# Interface.net
KiCad netlist of a schematic drawn in Altium Designer
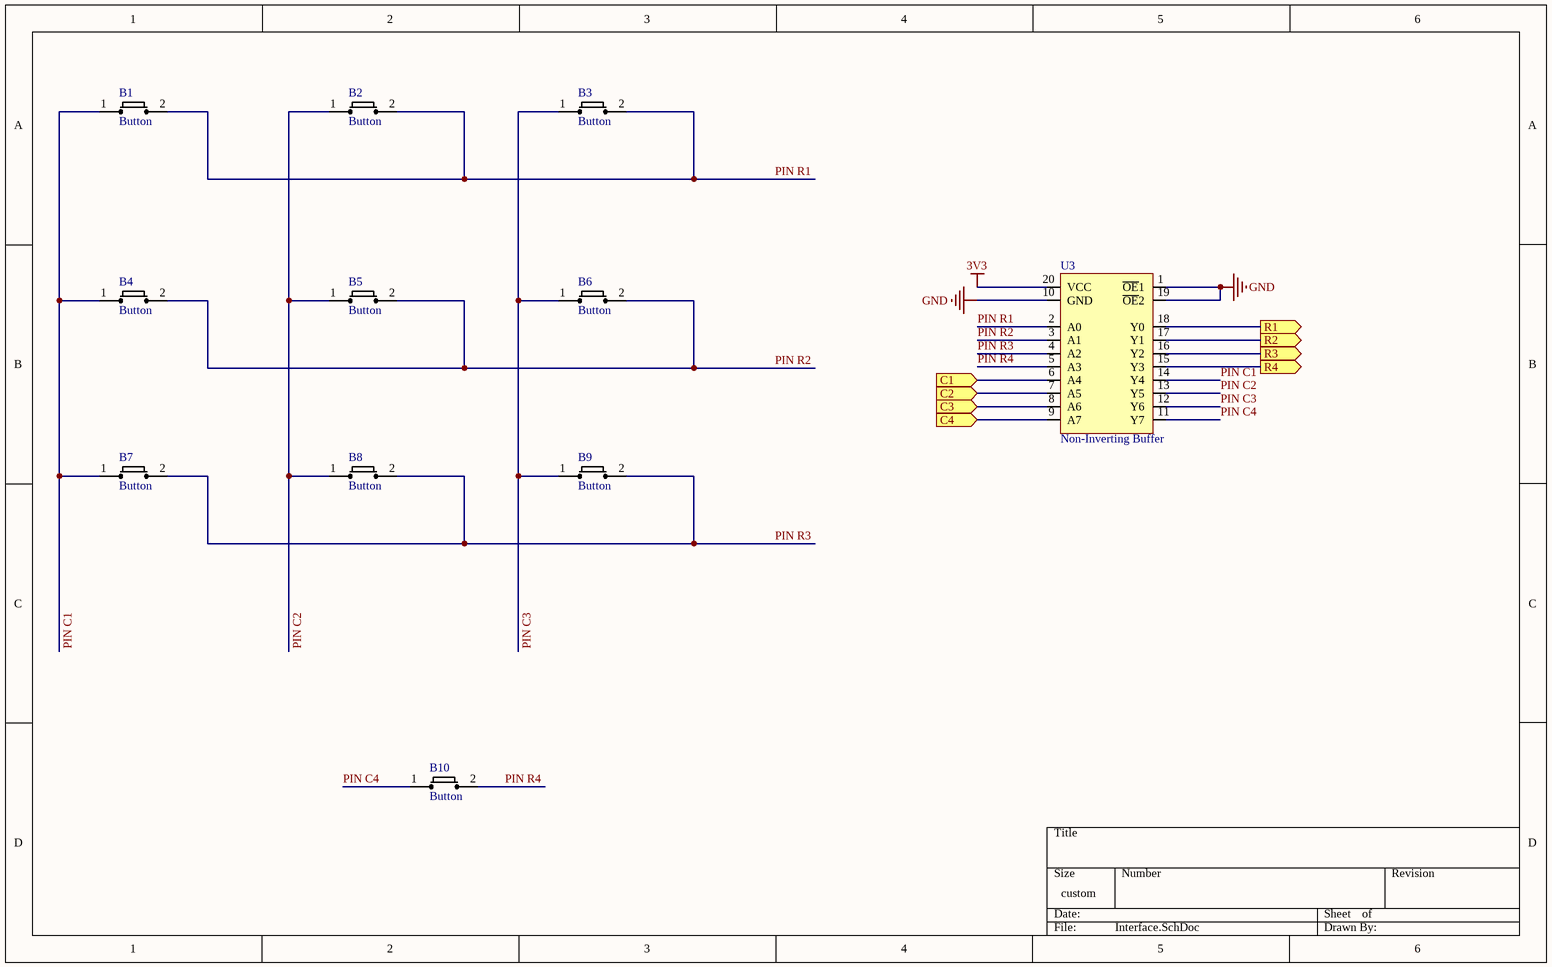
[diagram p0: Interface.SchDoc]

(export (version "E")
  (design (tool "Eeschema 10.0.6"))
  (components
    (comp (ref "B1")
      (value "Button")
      (footprint "BUTTON_B3F_SMD")
      (description "6x6mm, TH, 2 Pins")
      (libsource (lib "Altium Lib") (part "Button"))
    )
    (comp (ref "B2")
      (value "Button")
      (footprint "BUTTON_B3F_SMD")
      (description "6x6mm, TH, 2 Pins")
      (libsource (lib "Altium Lib") (part "Button"))
    )
    (comp (ref "B3")
      (value "Button")
      (footprint "BUTTON_B3F_SMD")
      (description "6x6mm, TH, 2 Pins")
      (libsource (lib "Altium Lib") (part "Button"))
    )
    (comp (ref "B4")
      (value "Button")
      (footprint "BUTTON_B3F_SMD")
      (description "6x6mm, TH, 2 Pins")
      (libsource (lib "Altium Lib") (part "Button"))
    )
    (comp (ref "B5")
      (value "Button")
      (footprint "BUTTON_B3F_SMD")
      (description "6x6mm, TH, 2 Pins")
      (libsource (lib "Altium Lib") (part "Button"))
    )
    (comp (ref "B6")
      (value "Button")
      (footprint "BUTTON_B3F_SMD")
      (description "6x6mm, TH, 2 Pins")
      (libsource (lib "Altium Lib") (part "Button"))
    )
    (comp (ref "B7")
      (value "Button")
      (footprint "BUTTON_B3F_SMD")
      (description "6x6mm, TH, 2 Pins")
      (libsource (lib "Altium Lib") (part "Button"))
    )
    (comp (ref "B8")
      (value "Button")
      (footprint "BUTTON_B3F_SMD")
      (description "6x6mm, TH, 2 Pins")
      (libsource (lib "Altium Lib") (part "Button"))
    )
    (comp (ref "B9")
      (value "Button")
      (footprint "BUTTON_B3F_SMD")
      (description "6x6mm, TH, 2 Pins")
      (libsource (lib "Altium Lib") (part "Button"))
    )
    (comp (ref "B10")
      (value "Button")
      (footprint "BUTTON_B3F_SMD")
      (description "6x6mm, TH, 2 Pins")
      (libsource (lib "Altium Lib") (part "Button"))
    )
    (comp (ref "U3")
      (value "Non-Inverting Buffer")
      (footprint "DIP_20")
      (libsource (lib "Altium Lib") (part "74HC541"))
    )
  )
  (nets
    (net (code "1") (name "/C1") (class "Default")
      (node (ref "U3") (pin "6") (pinfunction "A4_6") (pintype "passive"))
    )
    (net (code "2") (name "/C2") (class "Default")
      (node (ref "U3") (pin "7") (pinfunction "A5_7") (pintype "passive"))
    )
    (net (code "3") (name "/C3") (class "Default")
      (node (ref "U3") (pin "8") (pinfunction "A6_8") (pintype "passive"))
    )
    (net (code "4") (name "/C4") (class "Default")
      (node (ref "U3") (pin "9") (pinfunction "A7_9") (pintype "passive"))
    )
    (net (code "5") (name "/PIN C1") (class "Default")
      (node (ref "B1") (pin "1") (pinfunction "1_1") (pintype "passive"))
      (node (ref "B4") (pin "1") (pinfunction "1_1") (pintype "passive"))
      (node (ref "B7") (pin "1") (pinfunction "1_1") (pintype "passive"))
      (node (ref "U3") (pin "14") (pinfunction "Y4_14") (pintype "passive"))
    )
    (net (code "6") (name "/PIN C2") (class "Default")
      (node (ref "B2") (pin "1") (pinfunction "1_1") (pintype "passive"))
      (node (ref "B5") (pin "1") (pinfunction "1_1") (pintype "passive"))
      (node (ref "B8") (pin "1") (pinfunction "1_1") (pintype "passive"))
      (node (ref "U3") (pin "13") (pinfunction "Y5_13") (pintype "passive"))
    )
    (net (code "7") (name "/PIN C3") (class "Default")
      (node (ref "B3") (pin "1") (pinfunction "1_1") (pintype "passive"))
      (node (ref "B6") (pin "1") (pinfunction "1_1") (pintype "passive"))
      (node (ref "B9") (pin "1") (pinfunction "1_1") (pintype "passive"))
      (node (ref "U3") (pin "12") (pinfunction "Y6_12") (pintype "passive"))
    )
    (net (code "8") (name "/PIN C4") (class "Default")
      (node (ref "B10") (pin "1") (pinfunction "1_1") (pintype "passive"))
      (node (ref "U3") (pin "11") (pinfunction "Y7_11") (pintype "passive"))
    )
    (net (code "9") (name "/PIN R1") (class "Default")
      (node (ref "B1") (pin "2") (pinfunction "2_2") (pintype "passive"))
      (node (ref "B2") (pin "2") (pinfunction "2_2") (pintype "passive"))
      (node (ref "B3") (pin "2") (pinfunction "2_2") (pintype "passive"))
      (node (ref "U3") (pin "2") (pinfunction "A0_2") (pintype "passive"))
    )
    (net (code "10") (name "/PIN R2") (class "Default")
      (node (ref "B4") (pin "2") (pinfunction "2_2") (pintype "passive"))
      (node (ref "B5") (pin "2") (pinfunction "2_2") (pintype "passive"))
      (node (ref "B6") (pin "2") (pinfunction "2_2") (pintype "passive"))
      (node (ref "U3") (pin "3") (pinfunction "A1_3") (pintype "passive"))
    )
    (net (code "11") (name "/PIN R3") (class "Default")
      (node (ref "B7") (pin "2") (pinfunction "2_2") (pintype "passive"))
      (node (ref "B8") (pin "2") (pinfunction "2_2") (pintype "passive"))
      (node (ref "B9") (pin "2") (pinfunction "2_2") (pintype "passive"))
      (node (ref "U3") (pin "4") (pinfunction "A2_4") (pintype "passive"))
    )
    (net (code "12") (name "/PIN R4") (class "Default")
      (node (ref "B10") (pin "2") (pinfunction "2_2") (pintype "passive"))
      (node (ref "U3") (pin "5") (pinfunction "A3_5") (pintype "passive"))
    )
    (net (code "13") (name "/R1") (class "Default")
      (node (ref "U3") (pin "18") (pinfunction "Y0_18") (pintype "passive"))
    )
    (net (code "14") (name "/R2") (class "Default")
      (node (ref "U3") (pin "17") (pinfunction "Y1_17") (pintype "passive"))
    )
    (net (code "15") (name "/R3") (class "Default")
      (node (ref "U3") (pin "16") (pinfunction "Y2_16") (pintype "passive"))
    )
    (net (code "16") (name "/R4") (class "Default")
      (node (ref "U3") (pin "15") (pinfunction "Y3_15") (pintype "passive"))
    )
    (net (code "17") (name "3V3") (class "Default")
      (node (ref "U3") (pin "20") (pinfunction "VCC_20") (pintype "passive"))
    )
    (net (code "18") (name "GND") (class "Default")
      (node (ref "U3") (pin "1") (pinfunction "~{OE}1_1") (pintype "passive"))
      (node (ref "U3") (pin "10") (pinfunction "GND_10") (pintype "passive"))
      (node (ref "U3") (pin "19") (pinfunction "~{OE}2_19") (pintype "passive"))
    )
  )
)
